# 1V65_LDO.net
KiCad netlist of a schematic drawn in Altium Designer
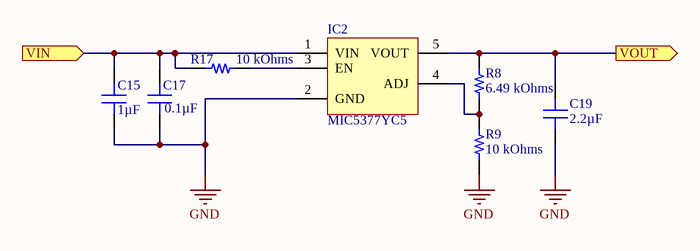
[diagram p0: 1V65_LDO.SchDoc]

(export (version "E")
  (design (tool "Eeschema 10.0.6"))
  (components
    (comp (ref "C15")
      (value "1µF")
      (footprint "CAP 0603_1608")
      (description "CAP CER 1UF 25V X7R 0603")
      (fields
        (field (name "PART NUMBER") "GCJ188R71E105KA01D")
        (field (name "MANUFACTURER") "Murata Electronics")
      )
      (libsource (lib "Celestial Altium Library - altium_library") (part "Capacitor"))
    )
    (comp (ref "C17")
      (value "0.1µF")
      (footprint "CAP 0603_1608")
      (description "CAP CER 0.1UF 100V 0603 EPOXY")
      (fields
        (field (name "PART NUMBER") "GCG188R92A104KA03D")
        (field (name "MANUFACTURER") "Murata Electronics")
      )
      (libsource (lib "Celestial Altium Library - altium_library") (part "Capacitor"))
    )
    (comp (ref "C19")
      (value "2.2µF")
      (footprint "CAP 0603_1608")
      (description "CAP CER 2.2UF 6.3V Y5V 0603")
      (fields (field (name "PART NUMBER") "CC0603ZRY5V5BB225") (field (name "MANUFACTURER") "Yageo"))
      (libsource (lib "Celestial Altium Library - altium_library") (part "Capacitor"))
    )
    (comp (ref "IC2")
      (value "MIC5377YC5")
      (footprint "TI SOT-23-5 DBV")
      (description "IC REG LIN POS ADJ 150MA SOT23-5")
      (fields (field (name "MANUFACTURER") "Texas Instruments"))
      (libsource (lib "IC") (part "MIC5377YC5"))
    )
    (comp (ref "R8")
      (value "6.49 kOhms")
      (footprint "RES 0603_1608")
      (description "RES SMD 6.49K OHM 1% 1/10W 0603")
      (fields (field (name "PART NUMBER") "RC0603FR-076K49L") (field (name "MANUFACTURER") "Yageo"))
      (libsource (lib "Celestial Altium Library - altium_library") (part "Resistor"))
    )
    (comp (ref "R9")
      (value "10 kOhms")
      (footprint "RES 0603_1608")
      (description "RES 10K OHM 0.1% 1/16W 0603")
      (fields
        (field (name "PART NUMBER") "RNCS0603BKE10K0")
        (field (name "MANUFACTURER") "Stackpole Electronics Inc")
      )
      (libsource (lib "Celestial Altium Library - altium_library") (part "Resistor"))
    )
    (comp (ref "R17")
      (value "10 kOhms")
      (footprint "RES 0603_1608")
      (description "RES 10K OHM 0.1% 1/16W 0603")
      (fields
        (field (name "PART NUMBER") "RNCS0603BKE10K0")
        (field (name "MANUFACTURER") "Stackpole Electronics Inc")
      )
      (libsource (lib "Celestial Altium Library - altium_library") (part "Resistor"))
    )
  )
  (nets
    (net (code "1") (name "/VIN") (class "Default")
      (node (ref "C15") (pin "2") (pinfunction "2_2") (pintype "passive"))
      (node (ref "C17") (pin "1") (pinfunction "1_1") (pintype "passive"))
      (node (ref "IC2") (pin "1") (pinfunction "VIN_1") (pintype "passive"))
      (node (ref "R17") (pin "2") (pinfunction "2_2") (pintype "passive"))
    )
    (net (code "2") (name "/VOUT") (class "Default")
      (node (ref "C19") (pin "2") (pinfunction "2_2") (pintype "passive"))
      (node (ref "IC2") (pin "5") (pinfunction "VOUT_5") (pintype "passive"))
      (node (ref "R8") (pin "2") (pinfunction "2_2") (pintype "passive"))
    )
    (net (code "3") (name "GND") (class "Default")
      (node (ref "C15") (pin "1") (pinfunction "1_1") (pintype "passive"))
      (node (ref "C17") (pin "2") (pinfunction "2_2") (pintype "passive"))
      (node (ref "C19") (pin "1") (pinfunction "1_1") (pintype "passive"))
      (node (ref "IC2") (pin "2") (pinfunction "GND_2") (pintype "passive"))
      (node (ref "R9") (pin "1") (pinfunction "1_1") (pintype "passive"))
    )
    (net (code "4") (name "Net-(IC2-ADJ)") (class "Default")
      (node (ref "IC2") (pin "4") (pinfunction "ADJ_4") (pintype "passive"))
      (node (ref "R8") (pin "1") (pinfunction "1_1") (pintype "passive"))
      (node (ref "R9") (pin "2") (pinfunction "2_2") (pintype "passive"))
    )
    (net (code "5") (name "Net-(IC2-EN)") (class "Default")
      (node (ref "IC2") (pin "3") (pinfunction "EN_3") (pintype "passive"))
      (node (ref "R17") (pin "1") (pinfunction "1_1") (pintype "passive"))
    )
  )
)
